# CCU-2-MCU.net
KiCad netlist of a schematic drawn in Altium Designer
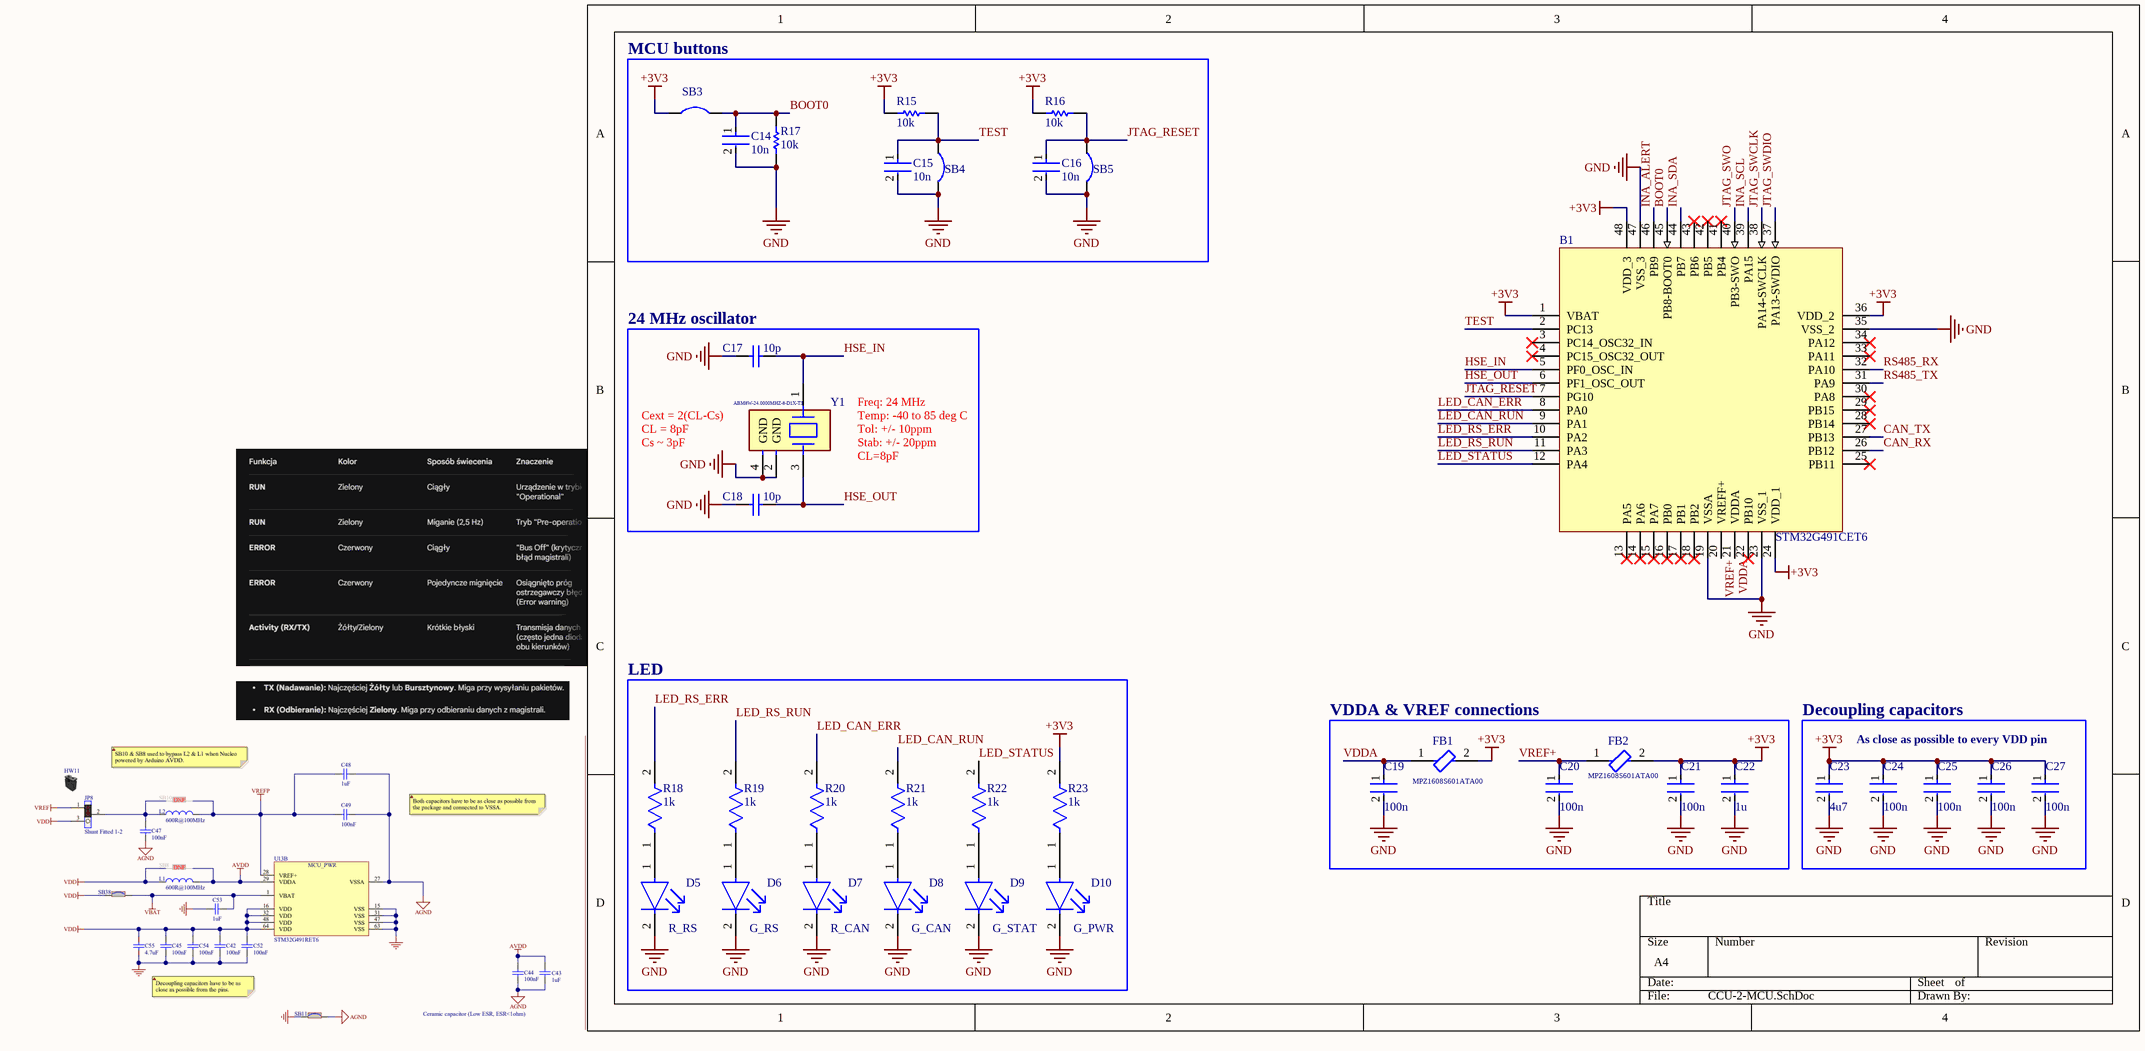
[diagram p0: CCU-2-MCU.SchDoc]

(export (version "E")
  (design (tool "Eeschema 10.0.6"))
  (components
    (comp (ref "B1")
      (value "STM32G491CET6")
      (footprint "STM32G491CET6")
      (description "ARM Microcontrollers - MCU Mainstream Arm Cortex-M4+ MCU 170MHz with 512Kbytes of Flash memory")
      (libsource (lib "HydrogreenLibrary") (part "STM32G491CET6"))
    )
    (comp (ref "C14")
      (value "10n")
      (footprint "FP-CC0603-DA-MFG")
      (description "CAP CER 10000PF 50V X7R 0603")
      (fields (field (name "TOLERANCE") "0.1") (field (name "MANUFACTURER PART NUMBER") "CC0603KRX7R9BB103"))
      (libsource (lib "Altium Content Vault") (part "11868f565c42a9108669ba33697ecf6"))
    )
    (comp (ref "C15")
      (value "10n")
      (footprint "FP-CC0603-DA-MFG")
      (description "CAP CER 10000PF 50V X7R 0603")
      (fields (field (name "TOLERANCE") "0.1") (field (name "MANUFACTURER PART NUMBER") "CC0603KRX7R9BB103"))
      (libsource (lib "Altium Content Vault") (part "11868f565c42a9108669ba33697ecf6"))
    )
    (comp (ref "C16")
      (value "10n")
      (footprint "FP-CC0603-DA-MFG")
      (description "CAP CER 10000PF 50V X7R 0603")
      (fields (field (name "TOLERANCE") "0.1") (field (name "MANUFACTURER PART NUMBER") "CC0603KRX7R9BB103"))
      (libsource (lib "Altium Content Vault") (part "11868f565c42a9108669ba33697ecf6"))
    )
    (comp (ref "C17")
      (value "10p")
      (footprint "CAPC1608X90X35LL10T15")
      (fields (field (name "PART NUMBER") "GRM1885C1H100JA01D") (field (name "MANUFACTURER") "Murata"))
      (libsource (lib "Altium Content Vault") (part "CAP"))
    )
    (comp (ref "C18")
      (value "10p")
      (footprint "CAPC1608X90X35LL10T15")
      (fields (field (name "PART NUMBER") "GRM1885C1H100JA01D") (field (name "MANUFACTURER") "Murata"))
      (libsource (lib "Altium Content Vault") (part "CAP"))
    )
    (comp (ref "C19")
      (value "100n")
      (footprint "FP-C0603C-CF-MFG")
      (description "CAP CER 0.1UF 25V X7R 0603")
      (fields
        (field (name "MANUFACTURER PART NUMBER") "C0603C104K3RACTU")
        (field (name "OCTOPART") "https://octopart.com/c0603c104k3ractu-kemet-127541")
      )
      (libsource (lib "Altium Content Vault") (part "b4654b650e69147ec39a6b967a45e02"))
    )
    (comp (ref "C20")
      (value "100n")
      (footprint "FP-C0603C-CF-MFG")
      (description "CAP CER 0.1UF 25V X7R 0603")
      (fields
        (field (name "MANUFACTURER PART NUMBER") "C0603C104K3RACTU")
        (field (name "OCTOPART") "https://octopart.com/c0603c104k3ractu-kemet-127541")
      )
      (libsource (lib "Altium Content Vault") (part "b4654b650e69147ec39a6b967a45e02"))
    )
    (comp (ref "C21")
      (value "100n")
      (footprint "FP-C0603C-CF-MFG")
      (description "CAP CER 0.1UF 25V X7R 0603")
      (fields
        (field (name "MANUFACTURER PART NUMBER") "C0603C104K3RACTU")
        (field (name "OCTOPART") "https://octopart.com/c0603c104k3ractu-kemet-127541")
      )
      (libsource (lib "Altium Content Vault") (part "b4654b650e69147ec39a6b967a45e02"))
    )
    (comp (ref "C22")
      (value "1u")
      (footprint "FP-CC0805-0_85-MFG")
      (description "CAP CER 1UF 25V X7R 0805")
      (fields (field (name "MANUFACTURER PART NUMBER") "CC0805KKX7R8BB105") (field (name "TOLERANCE") "0.1"))
      (libsource (lib "Altium Content Vault") (part "11868f565c42a9108669ba33697ecf6"))
    )
    (comp (ref "C23")
      (value "4u7")
      (footprint "FP-GRM21B-0_15-IPC_C")
      (description "Chip Multilayer Ceramic Capacitors for General Purpose, 0805, 4.7uF, X7R, 15%, 10%, 16V")
      (fields (field (name "TOLERANCE") "10%"))
      (libsource (lib "Altium Content Vault") (part "b4654b650e69147ec39a6b967a45e02"))
    )
    (comp (ref "C24")
      (value "100n")
      (footprint "FP-C0603C-CF-MFG")
      (description "CAP CER 0.1UF 25V X7R 0603")
      (fields
        (field (name "MANUFACTURER PART NUMBER") "C0603C104K3RACTU")
        (field (name "OCTOPART") "https://octopart.com/c0603c104k3ractu-kemet-127541")
      )
      (libsource (lib "Altium Content Vault") (part "b4654b650e69147ec39a6b967a45e02"))
    )
    (comp (ref "C25")
      (value "100n")
      (footprint "FP-C0603C-CF-MFG")
      (description "CAP CER 0.1UF 25V X7R 0603")
      (fields
        (field (name "MANUFACTURER PART NUMBER") "C0603C104K3RACTU")
        (field (name "OCTOPART") "https://octopart.com/c0603c104k3ractu-kemet-127541")
      )
      (libsource (lib "Altium Content Vault") (part "b4654b650e69147ec39a6b967a45e02"))
    )
    (comp (ref "C26")
      (value "100n")
      (footprint "FP-C0603C-CF-MFG")
      (description "CAP CER 0.1UF 25V X7R 0603")
      (fields
        (field (name "MANUFACTURER PART NUMBER") "C0603C104K3RACTU")
        (field (name "OCTOPART") "https://octopart.com/c0603c104k3ractu-kemet-127541")
      )
      (libsource (lib "Altium Content Vault") (part "b4654b650e69147ec39a6b967a45e02"))
    )
    (comp (ref "C27")
      (value "100n")
      (footprint "FP-C0603C-CF-MFG")
      (description "CAP CER 0.1UF 25V X7R 0603")
      (fields
        (field (name "MANUFACTURER PART NUMBER") "C0603C104K3RACTU")
        (field (name "OCTOPART") "https://octopart.com/c0603c104k3ractu-kemet-127541")
      )
      (libsource (lib "Altium Content Vault") (part "b4654b650e69147ec39a6b967a45e02"))
    )
    (comp (ref "D5")
      (value "R_RS")
      (footprint "FP-APT2012MGC-MFG")
      (description "LED GREEN CLEAR CHIP SMD")
      (libsource (lib "Altium Content Vault") (part "ab1c01a81903e929fc6c44469aada92"))
    )
    (comp (ref "D6")
      (value "G_RS")
      (footprint "FP-APT2012MGC-MFG")
      (description "LED GREEN CLEAR CHIP SMD")
      (libsource (lib "Altium Content Vault") (part "ab1c01a81903e929fc6c44469aada92"))
    )
    (comp (ref "D7")
      (value "R_CAN")
      (footprint "FP-APT2012MGC-MFG")
      (description "LED GREEN CLEAR CHIP SMD")
      (libsource (lib "Altium Content Vault") (part "ab1c01a81903e929fc6c44469aada92"))
    )
    (comp (ref "D8")
      (value "G_CAN")
      (footprint "FP-APT2012MGC-MFG")
      (description "LED GREEN CLEAR CHIP SMD")
      (libsource (lib "Altium Content Vault") (part "ab1c01a81903e929fc6c44469aada92"))
    )
    (comp (ref "D9")
      (value "G_STAT")
      (footprint "FP-APT2012MGC-MFG")
      (description "LED GREEN CLEAR CHIP SMD")
      (libsource (lib "Altium Content Vault") (part "ab1c01a81903e929fc6c44469aada92"))
    )
    (comp (ref "D10")
      (value "G_PWR")
      (footprint "FP-APT2012MGC-MFG")
      (description "LED GREEN CLEAR CHIP SMD")
      (libsource (lib "Altium Content Vault") (part "ab1c01a81903e929fc6c44469aada92"))
    )
    (comp (ref "FB1")
      (value "MPZ1608S601ATA00")
      (footprint "FP-MPZ1608-0_8-MFG")
      (description "Power line Ferrite Bead 600Ω @ 100MHz 1A DCR 0.15Ω SMD 0603")
      (fields (field (name "TOLERANCE") "25%"))
      (libsource (lib "Altium Content Vault") (part "5f30dd21d616792df468990f7003faa"))
    )
    (comp (ref "FB2")
      (value "MPZ1608S601ATA00")
      (footprint "FP-MPZ1608-0_8-MFG")
      (description "Power line Ferrite Bead 600Ω @ 100MHz 1A DCR 0.15Ω SMD 0603")
      (fields (field (name "TOLERANCE") "25%"))
      (libsource (lib "Altium Content Vault") (part "5f30dd21d616792df468990f7003faa"))
    )
    (comp (ref "R15")
      (value "10k")
      (footprint "RESC1608X55X25ML10T15")
      (description "Resistor, 10 KOhm, +/- 5%, 100 mW, -55 to 155 degC, 0603 (1608 Metric), RoHS, Tape and Reel")
      (fields (field (name "MANUFACTURER") "Yageo") (field (name "TOLERANCE") "5%"))
      (libsource (lib "Altium Content Vault") (part "RES-2"))
    )
    (comp (ref "R16")
      (value "10k")
      (footprint "RESC1608X55X25ML10T15")
      (description "Resistor, 10 KOhm, +/- 5%, 100 mW, -55 to 155 degC, 0603 (1608 Metric), RoHS, Tape and Reel")
      (fields (field (name "MANUFACTURER") "Yageo") (field (name "TOLERANCE") "5%"))
      (libsource (lib "Altium Content Vault") (part "RES-2"))
    )
    (comp (ref "R17")
      (value "10k")
      (footprint "RESC1608X55X25ML10T15")
      (description "Resistor, 10 KOhm, +/- 5%, 100 mW, -55 to 155 degC, 0603 (1608 Metric), RoHS, Tape and Reel")
      (fields (field (name "MANUFACTURER") "Yageo") (field (name "TOLERANCE") "5%"))
      (libsource (lib "Altium Content Vault") (part "RES-2"))
    )
    (comp (ref "R18")
      (value "1k")
      (footprint "FP-RC0603-0_55-IPC_C")
      (description "RES 1K OHM 1% 1/10W 0603")
      (fields (field (name "TOLERANCE") "1%"))
      (libsource (lib "Altium Content Vault") (part "1029c3af85768c4190bb7ad29bc67b5"))
    )
    (comp (ref "R19")
      (value "1k")
      (footprint "FP-RC0603-0_55-IPC_C")
      (description "RES 1K OHM 1% 1/10W 0603")
      (fields (field (name "TOLERANCE") "1%"))
      (libsource (lib "Altium Content Vault") (part "1029c3af85768c4190bb7ad29bc67b5"))
    )
    (comp (ref "R20")
      (value "1k")
      (footprint "FP-RC0603-0_55-IPC_C")
      (description "RES 1K OHM 1% 1/10W 0603")
      (fields (field (name "TOLERANCE") "1%"))
      (libsource (lib "Altium Content Vault") (part "1029c3af85768c4190bb7ad29bc67b5"))
    )
    (comp (ref "R21")
      (value "1k")
      (footprint "FP-RC0603-0_55-IPC_C")
      (description "RES 1K OHM 1% 1/10W 0603")
      (fields (field (name "TOLERANCE") "1%"))
      (libsource (lib "Altium Content Vault") (part "1029c3af85768c4190bb7ad29bc67b5"))
    )
    (comp (ref "R22")
      (value "1k")
      (footprint "FP-RC0603-0_55-IPC_C")
      (description "RES 1K OHM 1% 1/10W 0603")
      (fields (field (name "TOLERANCE") "1%"))
      (libsource (lib "Altium Content Vault") (part "1029c3af85768c4190bb7ad29bc67b5"))
    )
    (comp (ref "R23")
      (value "1k")
      (footprint "FP-RC0603-0_55-IPC_C")
      (description "RES 1K OHM 1% 1/10W 0603")
      (fields (field (name "TOLERANCE") "1%"))
      (libsource (lib "Altium Content Vault") (part "1029c3af85768c4190bb7ad29bc67b5"))
    )
    (comp (ref "SB3")
      (value "Solder_Bridge")
      (footprint "Solder Bridge")
      (description "Bridge 0.5mm gap, 2mm width")
      (libsource (lib "HydrogreenLibrary") (part "Solder_Bridge"))
    )
    (comp (ref "SB4")
      (value "Solder_Bridge")
      (footprint "Solder Bridge")
      (description "Bridge 0.5mm gap, 2mm width")
      (libsource (lib "") (part "Solder_Bridge_1"))
    )
    (comp (ref "SB5")
      (value "Solder_Bridge")
      (footprint "Solder Bridge")
      (description "Bridge 0.5mm gap, 2mm width")
      (libsource (lib "") (part "Solder_Bridge_1"))
    )
    (comp (ref "Y1")
      (value "ABM8W-24.0000MHZ-8-D1X-T3")
      (footprint "FP-ABM8W-MFG")
      (description "Crystal 24MHz ±10ppm (Tol) ±20ppm (Stability) 8pF FUND 50Ω 4-Pin SMD T/R")
      (libsource (lib "Altium Content Vault") (part "41079aabb0e87794b56622915be14ed"))
    )
  )
  (nets
    (net (code "1") (name "+3V3") (class "Default")
      (node (ref "B1") (pin "1") (pinfunction "VBAT_1") (pintype "passive"))
      (node (ref "B1") (pin "24") (pinfunction "VDD_1_24") (pintype "passive"))
      (node (ref "B1") (pin "36") (pinfunction "VDD_2_36") (pintype "passive"))
      (node (ref "B1") (pin "48") (pinfunction "VDD_3_48") (pintype "passive"))
      (node (ref "C21") (pin "1") (pinfunction "1_1") (pintype "passive"))
      (node (ref "C22") (pin "1") (pinfunction "1_1") (pintype "passive"))
      (node (ref "C23") (pin "1") (pinfunction "1_1") (pintype "passive"))
      (node (ref "C24") (pin "1") (pinfunction "1_1") (pintype "passive"))
      (node (ref "C25") (pin "1") (pinfunction "1_1") (pintype "passive"))
      (node (ref "C26") (pin "1") (pinfunction "1_1") (pintype "passive"))
      (node (ref "C27") (pin "1") (pinfunction "1_1") (pintype "passive"))
      (node (ref "FB1") (pin "2") (pinfunction "2_2") (pintype "passive"))
      (node (ref "FB2") (pin "2") (pinfunction "2_2") (pintype "passive"))
      (node (ref "R15") (pin "2") (pinfunction "2_2") (pintype "passive"))
      (node (ref "R16") (pin "2") (pinfunction "2_2") (pintype "passive"))
      (node (ref "R23") (pin "2") (pinfunction "2_2") (pintype "passive"))
      (node (ref "SB3") (pin "1") (pinfunction "1_1") (pintype "passive"))
    )
    (net (code "2") (name "/BOOT0") (class "Default")
      (node (ref "B1") (pin "45") (pinfunction "PB8-BOOT0_45") (pintype "input"))
      (node (ref "C14") (pin "1") (pinfunction "1_1") (pintype "passive"))
      (node (ref "R17") (pin "2") (pinfunction "2_2") (pintype "passive"))
      (node (ref "SB3") (pin "2") (pinfunction "2_2") (pintype "passive"))
    )
    (net (code "3") (name "/CAN_RX") (class "Default")
      (node (ref "B1") (pin "26") (pinfunction "PB12_26") (pintype "passive"))
    )
    (net (code "4") (name "/CAN_TX") (class "Default")
      (node (ref "B1") (pin "27") (pinfunction "PB13_27") (pintype "passive"))
    )
    (net (code "5") (name "/HSE_IN") (class "Default")
      (node (ref "B1") (pin "5") (pinfunction "PF0_OSC_IN_5") (pintype "passive"))
      (node (ref "C17") (pin "2") (pinfunction "2_2") (pintype "passive"))
      (node (ref "Y1") (pin "1") (pinfunction "1_1") (pintype "passive"))
    )
    (net (code "6") (name "/HSE_OUT") (class "Default")
      (node (ref "B1") (pin "6") (pinfunction "PF1_OSC_OUT_6") (pintype "passive"))
      (node (ref "C18") (pin "2") (pinfunction "2_2") (pintype "passive"))
      (node (ref "Y1") (pin "3") (pinfunction "3_3") (pintype "passive"))
    )
    (net (code "7") (name "/INA_ALERT") (class "Default")
      (node (ref "B1") (pin "46") (pinfunction "PB9_46") (pintype "passive"))
    )
    (net (code "8") (name "/INA_SCL") (class "Default")
      (node (ref "B1") (pin "39") (pinfunction "PA15_39") (pintype "passive"))
    )
    (net (code "9") (name "/INA_SDA") (class "Default")
      (node (ref "B1") (pin "44") (pinfunction "PB7_44") (pintype "passive"))
    )
    (net (code "10") (name "/JTAG_RESET") (class "Default")
      (node (ref "B1") (pin "7") (pinfunction "PG10_7") (pintype "passive"))
      (node (ref "C16") (pin "1") (pinfunction "1_1") (pintype "passive"))
      (node (ref "R16") (pin "1") (pinfunction "1_1") (pintype "passive"))
      (node (ref "SB5") (pin "1") (pinfunction "1_1") (pintype "passive"))
    )
    (net (code "11") (name "/JTAG_SWCLK") (class "Default")
      (node (ref "B1") (pin "38") (pinfunction "PA14-SWCLK_38") (pintype "input"))
    )
    (net (code "12") (name "/JTAG_SWDIO") (class "Default")
      (node (ref "B1") (pin "37") (pinfunction "PA13-SWDIO_37") (pintype "input"))
    )
    (net (code "13") (name "/JTAG_SWO") (class "Default")
      (node (ref "B1") (pin "40") (pinfunction "PB3-SWO_40") (pintype "input"))
    )
    (net (code "14") (name "/LED_CAN_ERR") (class "Default")
      (node (ref "B1") (pin "8") (pinfunction "PA0_8") (pintype "passive"))
      (node (ref "R20") (pin "2") (pinfunction "2_2") (pintype "passive"))
    )
    (net (code "15") (name "/LED_CAN_RUN") (class "Default")
      (node (ref "B1") (pin "9") (pinfunction "PA1_9") (pintype "passive"))
      (node (ref "R21") (pin "2") (pinfunction "2_2") (pintype "passive"))
    )
    (net (code "16") (name "/LED_RS_ERR") (class "Default")
      (node (ref "B1") (pin "10") (pinfunction "PA2_10") (pintype "passive"))
      (node (ref "R18") (pin "2") (pinfunction "2_2") (pintype "passive"))
    )
    (net (code "17") (name "/LED_RS_RUN") (class "Default")
      (node (ref "B1") (pin "11") (pinfunction "PA3_11") (pintype "passive"))
      (node (ref "R19") (pin "2") (pinfunction "2_2") (pintype "passive"))
    )
    (net (code "18") (name "/LED_STATUS") (class "Default")
      (node (ref "B1") (pin "12") (pinfunction "PA4_12") (pintype "passive"))
      (node (ref "R22") (pin "2") (pinfunction "2_2") (pintype "passive"))
    )
    (net (code "19") (name "/RS485_RX") (class "Default")
      (node (ref "B1") (pin "32") (pinfunction "PA10_32") (pintype "passive"))
    )
    (net (code "20") (name "/RS485_TX") (class "Default")
      (node (ref "B1") (pin "31") (pinfunction "PA9_31") (pintype "passive"))
    )
    (net (code "21") (name "/TEST") (class "Default")
      (node (ref "B1") (pin "2") (pinfunction "PC13_2") (pintype "passive"))
      (node (ref "C15") (pin "1") (pinfunction "1_1") (pintype "passive"))
      (node (ref "R15") (pin "1") (pinfunction "1_1") (pintype "passive"))
      (node (ref "SB4") (pin "1") (pinfunction "1_1") (pintype "passive"))
    )
    (net (code "22") (name "/VDDA") (class "Default")
      (node (ref "B1") (pin "21") (pinfunction "VDDA_21") (pintype "passive"))
      (node (ref "C19") (pin "1") (pinfunction "1_1") (pintype "passive"))
      (node (ref "FB1") (pin "1") (pinfunction "1_1") (pintype "passive"))
    )
    (net (code "23") (name "/VREF+") (class "Default")
      (node (ref "B1") (pin "20") (pinfunction "VREFF+_20") (pintype "passive"))
      (node (ref "C20") (pin "1") (pinfunction "1_1") (pintype "passive"))
      (node (ref "FB2") (pin "1") (pinfunction "1_1") (pintype "passive"))
    )
    (net (code "24") (name "GND") (class "Default")
      (node (ref "B1") (pin "19") (pinfunction "VSSA_19") (pintype "passive"))
      (node (ref "B1") (pin "23") (pinfunction "VSS_1_23") (pintype "passive"))
      (node (ref "B1") (pin "35") (pinfunction "VSS_2_35") (pintype "passive"))
      (node (ref "B1") (pin "47") (pinfunction "VSS_3_47") (pintype "passive"))
      (node (ref "C14") (pin "2") (pinfunction "2_2") (pintype "passive"))
      (node (ref "C15") (pin "2") (pinfunction "2_2") (pintype "passive"))
      (node (ref "C16") (pin "2") (pinfunction "2_2") (pintype "passive"))
      (node (ref "C17") (pin "1") (pinfunction "1_1") (pintype "passive"))
      (node (ref "C18") (pin "1") (pinfunction "1_1") (pintype "passive"))
      (node (ref "C19") (pin "2") (pinfunction "2_2") (pintype "passive"))
      (node (ref "C20") (pin "2") (pinfunction "2_2") (pintype "passive"))
      (node (ref "C21") (pin "2") (pinfunction "2_2") (pintype "passive"))
      (node (ref "C22") (pin "2") (pinfunction "2_2") (pintype "passive"))
      (node (ref "C23") (pin "2") (pinfunction "2_2") (pintype "passive"))
      (node (ref "C24") (pin "2") (pinfunction "2_2") (pintype "passive"))
      (node (ref "C25") (pin "2") (pinfunction "2_2") (pintype "passive"))
      (node (ref "C26") (pin "2") (pinfunction "2_2") (pintype "passive"))
      (node (ref "C27") (pin "2") (pinfunction "2_2") (pintype "passive"))
      (node (ref "D10") (pin "2") (pinfunction "C_2") (pintype "passive"))
      (node (ref "D5") (pin "2") (pinfunction "C_2") (pintype "passive"))
      (node (ref "D6") (pin "2") (pinfunction "C_2") (pintype "passive"))
      (node (ref "D7") (pin "2") (pinfunction "C_2") (pintype "passive"))
      (node (ref "D8") (pin "2") (pinfunction "C_2") (pintype "passive"))
      (node (ref "D9") (pin "2") (pinfunction "C_2") (pintype "passive"))
      (node (ref "R17") (pin "1") (pinfunction "1_1") (pintype "passive"))
      (node (ref "SB4") (pin "2") (pinfunction "2_2") (pintype "passive"))
      (node (ref "SB5") (pin "2") (pinfunction "2_2") (pintype "passive"))
      (node (ref "Y1") (pin "2") (pinfunction "GND_2") (pintype "power_in"))
      (node (ref "Y1") (pin "4") (pinfunction "GND_4") (pintype "power_in"))
    )
    (net (code "25") (name "Net-(D5-A)") (class "Default")
      (node (ref "D5") (pin "1") (pinfunction "A_1") (pintype "passive"))
      (node (ref "R18") (pin "1") (pinfunction "1_1") (pintype "passive"))
    )
    (net (code "26") (name "Net-(D6-A)") (class "Default")
      (node (ref "D6") (pin "1") (pinfunction "A_1") (pintype "passive"))
      (node (ref "R19") (pin "1") (pinfunction "1_1") (pintype "passive"))
    )
    (net (code "27") (name "Net-(D7-A)") (class "Default")
      (node (ref "D7") (pin "1") (pinfunction "A_1") (pintype "passive"))
      (node (ref "R20") (pin "1") (pinfunction "1_1") (pintype "passive"))
    )
    (net (code "28") (name "Net-(D8-A)") (class "Default")
      (node (ref "D8") (pin "1") (pinfunction "A_1") (pintype "passive"))
      (node (ref "R21") (pin "1") (pinfunction "1_1") (pintype "passive"))
    )
    (net (code "29") (name "Net-(D9-A)") (class "Default")
      (node (ref "D9") (pin "1") (pinfunction "A_1") (pintype "passive"))
      (node (ref "R22") (pin "1") (pinfunction "1_1") (pintype "passive"))
    )
    (net (code "30") (name "Net-(D10-A)") (class "Default")
      (node (ref "D10") (pin "1") (pinfunction "A_1") (pintype "passive"))
      (node (ref "R23") (pin "1") (pinfunction "1_1") (pintype "passive"))
    )
    (net (code "31") (name "unconnected-(B1-PA5-Pad13)") (class "Default")
      (node (ref "B1") (pin "13") (pinfunction "PA5_13") (pintype "passive+no_connect"))
    )
    (net (code "32") (name "unconnected-(B1-PA6-Pad14)") (class "Default")
      (node (ref "B1") (pin "14") (pinfunction "PA6_14") (pintype "passive+no_connect"))
    )
    (net (code "33") (name "unconnected-(B1-PA7-Pad15)") (class "Default")
      (node (ref "B1") (pin "15") (pinfunction "PA7_15") (pintype "passive+no_connect"))
    )
    (net (code "34") (name "unconnected-(B1-PA8-Pad30)") (class "Default")
      (node (ref "B1") (pin "30") (pinfunction "PA8_30") (pintype "passive+no_connect"))
    )
    (net (code "35") (name "unconnected-(B1-PA11-Pad33)") (class "Default")
      (node (ref "B1") (pin "33") (pinfunction "PA11_33") (pintype "passive+no_connect"))
    )
    (net (code "36") (name "unconnected-(B1-PA12-Pad34)") (class "Default")
      (node (ref "B1") (pin "34") (pinfunction "PA12_34") (pintype "passive+no_connect"))
    )
    (net (code "37") (name "unconnected-(B1-PB0-Pad16)") (class "Default")
      (node (ref "B1") (pin "16") (pinfunction "PB0_16") (pintype "passive+no_connect"))
    )
    (net (code "38") (name "unconnected-(B1-PB1-Pad17)") (class "Default")
      (node (ref "B1") (pin "17") (pinfunction "PB1_17") (pintype "passive+no_connect"))
    )
    (net (code "39") (name "unconnected-(B1-PB2-Pad18)") (class "Default")
      (node (ref "B1") (pin "18") (pinfunction "PB2_18") (pintype "passive+no_connect"))
    )
    (net (code "40") (name "unconnected-(B1-PB4-Pad41)") (class "Default")
      (node (ref "B1") (pin "41") (pinfunction "PB4_41") (pintype "passive+no_connect"))
    )
    (net (code "41") (name "unconnected-(B1-PB5-Pad42)") (class "Default")
      (node (ref "B1") (pin "42") (pinfunction "PB5_42") (pintype "passive+no_connect"))
    )
    (net (code "42") (name "unconnected-(B1-PB6-Pad43)") (class "Default")
      (node (ref "B1") (pin "43") (pinfunction "PB6_43") (pintype "passive+no_connect"))
    )
    (net (code "43") (name "unconnected-(B1-PB10-Pad22)") (class "Default")
      (node (ref "B1") (pin "22") (pinfunction "PB10_22") (pintype "passive+no_connect"))
    )
    (net (code "44") (name "unconnected-(B1-PB11-Pad25)") (class "Default")
      (node (ref "B1") (pin "25") (pinfunction "PB11_25") (pintype "passive+no_connect"))
    )
    (net (code "45") (name "unconnected-(B1-PB14-Pad28)") (class "Default")
      (node (ref "B1") (pin "28") (pinfunction "PB14_28") (pintype "passive+no_connect"))
    )
    (net (code "46") (name "unconnected-(B1-PB15-Pad29)") (class "Default")
      (node (ref "B1") (pin "29") (pinfunction "PB15_29") (pintype "passive+no_connect"))
    )
    (net (code "47") (name "unconnected-(B1-PC14_OSC32_IN-Pad3)") (class "Default")
      (node (ref "B1") (pin "3") (pinfunction "PC14_OSC32_IN_3") (pintype "passive+no_connect"))
    )
    (net (code "48") (name "unconnected-(B1-PC15_OSC32_OUT-Pad4)") (class "Default")
      (node (ref "B1") (pin "4") (pinfunction "PC15_OSC32_OUT_4") (pintype "passive+no_connect"))
    )
  )
)
